# CTRL_Paws.net
KiCad netlist of a schematic drawn in EasyEDA Pro
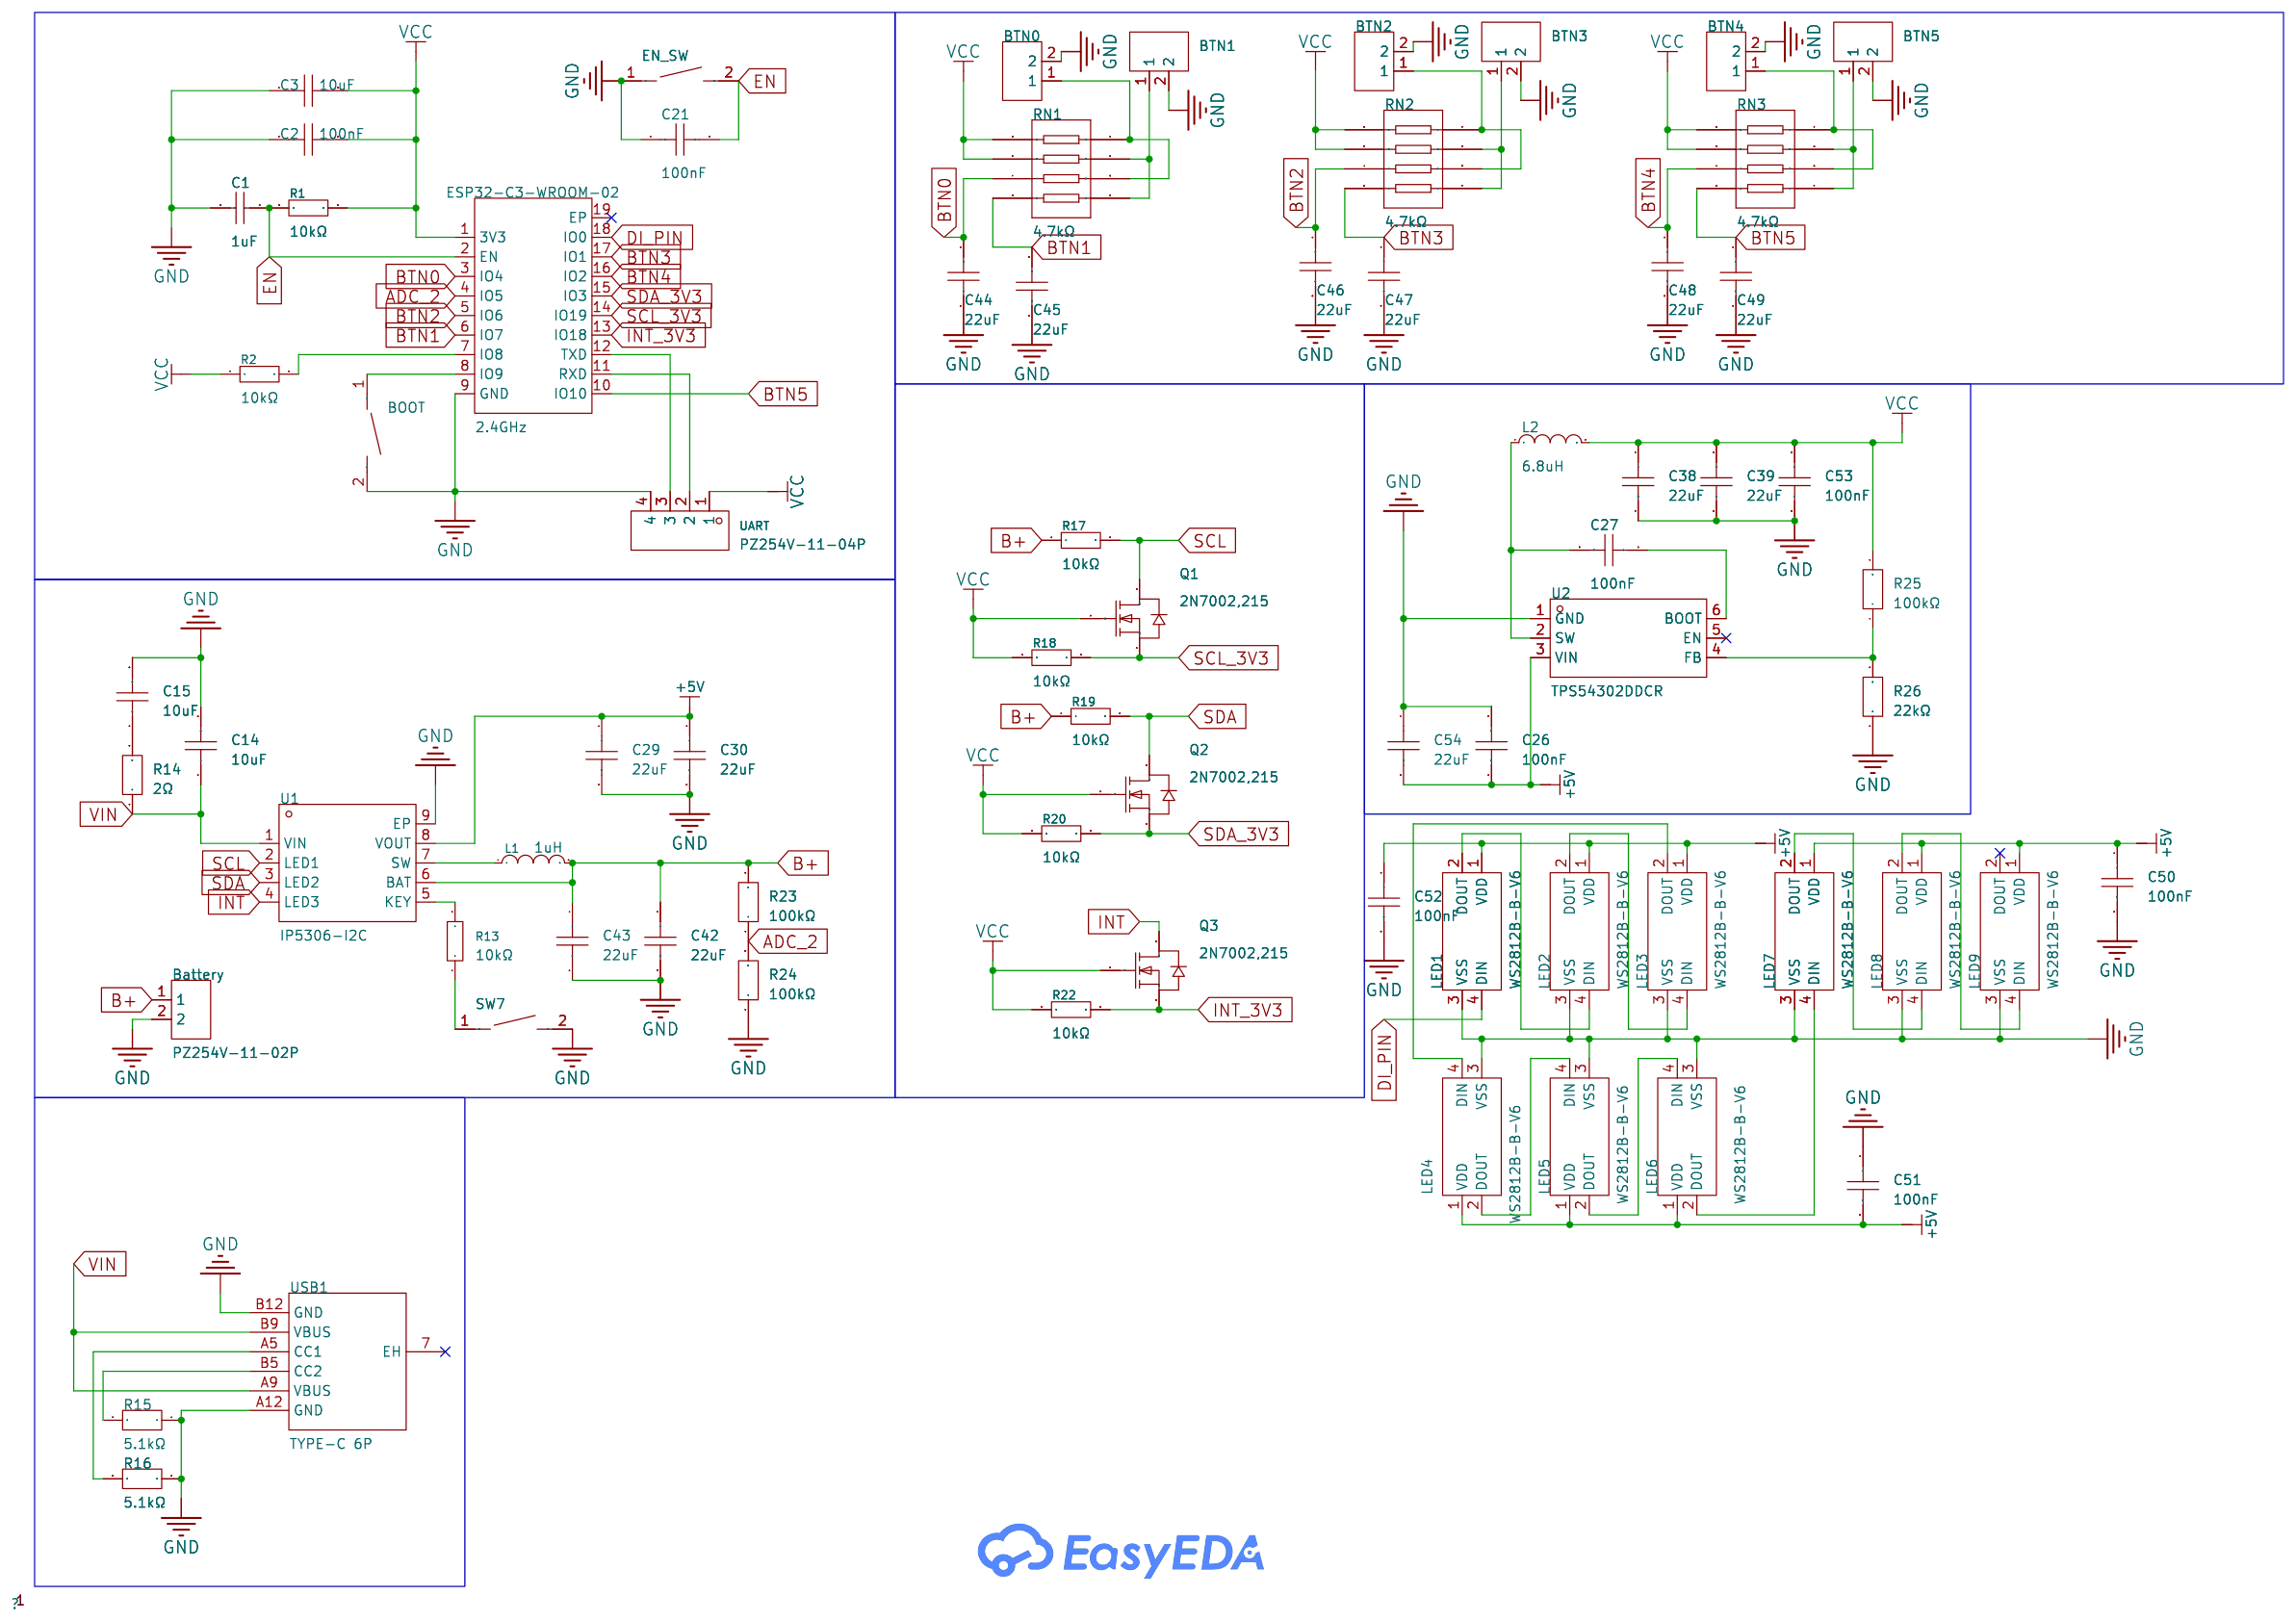
[diagram p0: schematic sheet]

(export (version "E")
  (design (tool "Eeschema 10.0.6"))
  (components
    (comp (ref "Battery")
      (value "PZ254V-11-02P")
      (footprint "easyedapro:HDR-TH_2P-P2.54-V-M")
      (fields (field (name "Manufacturer") "XFCN(兴飞)"))
      (libsource (lib "easyedapro") (part "PZ254V-11-02P"))
    )
    (comp (ref "BOOT")
      (value "TSA06154-050B832BA")
      (footprint "easyedapro:SW-TH_L6.1-W6.1-P5.00")
      (fields (field (name "Manufacturer") "Khon(康宏电子)"))
      (libsource (lib "easyedapro") (part "TSA06154-050B832BA"))
    )
    (comp (ref "BTN0")
      (value "PZ254V-11-02P")
      (footprint "easyedapro:HDR-TH_2P-P2.54-V-M")
      (fields (field (name "Manufacturer") "XFCN(兴飞)"))
      (libsource (lib "easyedapro") (part "PZ254V-11-02P"))
    )
    (comp (ref "BTN1")
      (value "PZ254V-11-02P")
      (footprint "easyedapro:HDR-TH_2P-P2.54-V-M")
      (fields (field (name "Manufacturer") "XFCN(兴飞)"))
      (libsource (lib "easyedapro") (part "PZ254V-11-02P"))
    )
    (comp (ref "BTN2")
      (value "PZ254V-11-02P")
      (footprint "easyedapro:HDR-TH_2P-P2.54-V-M")
      (fields (field (name "Manufacturer") "XFCN(兴飞)"))
      (libsource (lib "easyedapro") (part "PZ254V-11-02P"))
    )
    (comp (ref "BTN3")
      (value "PZ254V-11-02P")
      (footprint "easyedapro:HDR-TH_2P-P2.54-V-M")
      (fields (field (name "Manufacturer") "XFCN(兴飞)"))
      (libsource (lib "easyedapro") (part "PZ254V-11-02P"))
    )
    (comp (ref "BTN4")
      (value "PZ254V-11-02P")
      (footprint "easyedapro:HDR-TH_2P-P2.54-V-M")
      (fields (field (name "Manufacturer") "XFCN(兴飞)"))
      (libsource (lib "easyedapro") (part "PZ254V-11-02P"))
    )
    (comp (ref "BTN5")
      (value "PZ254V-11-02P")
      (footprint "easyedapro:HDR-TH_2P-P2.54-V-M")
      (fields (field (name "Manufacturer") "XFCN(兴飞)"))
      (libsource (lib "easyedapro") (part "PZ254V-11-02P"))
    )
    (comp (ref "C1")
      (value "1uF")
      (footprint "easyedapro:C0603")
      (description "Capacitance:1uF Tolerance:±10% Tolerance:±10% Voltage Rating:16V Temperature Coefficient:X7R")
      (fields
        (field (name "Manufacturer Part") "CL10B105KO8NNNC")
        (field (name "Manufacturer") "SAMSUNG(三星)")
      )
      (libsource (lib "easyedapro") (part "CL10B105KO8NNNC"))
    )
    (comp (ref "C2")
      (value "100nF")
      (footprint "easyedapro:C1206")
      (description "Capacitance:100nF Tolerance:±10% Tolerance:±10% Voltage Rating:16V Temperature Coefficient:X7R")
      (fields
        (field (name "Manufacturer Part") "CC1206KRX7R7BB104")
        (field (name "Manufacturer") "YAGEO(国巨)")
      )
      (libsource (lib "easyedapro") (part "CC1206KRX7R7BB104"))
    )
    (comp (ref "C3")
      (value "10uF")
      (footprint "easyedapro:C0603")
      (description "Capacitance:10uF Tolerance:±10% Tolerance:±10% Voltage Rating:16V Temperature Coefficient:X5R")
      (fields
        (field (name "Manufacturer Part") "CL10A106KO8NQNC")
        (field (name "Manufacturer") "SAMSUNG(三星)")
      )
      (libsource (lib "easyedapro") (part "CL10A106KO8NQNC"))
    )
    (comp (ref "C14")
      (value "10uF")
      (footprint "easyedapro:C0603")
      (description "Capacitance:10uF Tolerance:±10% Tolerance:±10% Voltage Rating:16V Temperature Coefficient:X5R")
      (fields
        (field (name "Manufacturer Part") "CL10A106KO8NQNC")
        (field (name "Manufacturer") "SAMSUNG(三星)")
      )
      (libsource (lib "easyedapro") (part "CL10A106KO8NQNC"))
    )
    (comp (ref "C15")
      (value "10uF")
      (footprint "easyedapro:C0603")
      (description "Capacitance:10uF Tolerance:±10% Tolerance:±10% Voltage Rating:16V Temperature Coefficient:X5R")
      (fields
        (field (name "Manufacturer Part") "CL10A106KO8NQNC")
        (field (name "Manufacturer") "SAMSUNG(三星)")
      )
      (libsource (lib "easyedapro") (part "CL10A106KO8NQNC"))
    )
    (comp (ref "C21")
      (value "100nF")
      (footprint "easyedapro:C1206")
      (description "Capacitance:100nF Tolerance:±10% Tolerance:±10% Voltage Rating:16V Temperature Coefficient:X7R")
      (fields
        (field (name "Manufacturer Part") "CC1206KRX7R7BB104")
        (field (name "Manufacturer") "YAGEO(国巨)")
      )
      (libsource (lib "easyedapro") (part "CC1206KRX7R7BB104"))
    )
    (comp (ref "C26")
      (value "100nF")
      (footprint "easyedapro:C1206")
      (description "Capacitance:100nF Tolerance:±10% Tolerance:±10% Voltage Rating:16V Temperature Coefficient:X7R")
      (fields
        (field (name "Manufacturer Part") "CC1206KRX7R7BB104")
        (field (name "Manufacturer") "YAGEO(国巨)")
      )
      (libsource (lib "easyedapro") (part "CC1206KRX7R7BB104"))
    )
    (comp (ref "C27")
      (value "100nF")
      (footprint "easyedapro:C1206")
      (description "Capacitance:100nF Tolerance:±10% Tolerance:±10% Voltage Rating:16V Temperature Coefficient:X7R")
      (fields
        (field (name "Manufacturer Part") "CC1206KRX7R7BB104")
        (field (name "Manufacturer") "YAGEO(国巨)")
      )
      (libsource (lib "easyedapro") (part "CC1206KRX7R7BB104"))
    )
    (comp (ref "C29")
      (value "22uF")
      (footprint "easyedapro:C0603")
      (description "Capacitance:22uF Tolerance:±20% Tolerance:±20% Voltage Rating:16V Temperature Coefficient:X5R")
      (fields
        (field (name "Manufacturer Part") "CL10A226MO7JZNC")
        (field (name "Manufacturer") "SAMSUNG(三星)")
      )
      (libsource (lib "easyedapro") (part "CL10A226MO7JZNC"))
    )
    (comp (ref "C30")
      (value "22uF")
      (footprint "easyedapro:C0603")
      (description "Capacitance:22uF Tolerance:±20% Tolerance:±20% Voltage Rating:16V Temperature Coefficient:X5R")
      (fields
        (field (name "Manufacturer Part") "CL10A226MO7JZNC")
        (field (name "Manufacturer") "SAMSUNG(三星)")
      )
      (libsource (lib "easyedapro") (part "CL10A226MO7JZNC"))
    )
    (comp (ref "C38")
      (value "22uF")
      (footprint "easyedapro:C0603")
      (description "Capacitance:22uF Tolerance:±20% Tolerance:±20% Voltage Rating:16V Temperature Coefficient:X5R")
      (fields
        (field (name "Manufacturer Part") "CL10A226MO7JZNC")
        (field (name "Manufacturer") "SAMSUNG(三星)")
      )
      (libsource (lib "easyedapro") (part "CL10A226MO7JZNC"))
    )
    (comp (ref "C39")
      (value "22uF")
      (footprint "easyedapro:C0603")
      (description "Capacitance:22uF Tolerance:±20% Tolerance:±20% Voltage Rating:16V Temperature Coefficient:X5R")
      (fields
        (field (name "Manufacturer Part") "CL10A226MO7JZNC")
        (field (name "Manufacturer") "SAMSUNG(三星)")
      )
      (libsource (lib "easyedapro") (part "CL10A226MO7JZNC"))
    )
    (comp (ref "C42")
      (value "22uF")
      (footprint "easyedapro:C0603")
      (description "Capacitance:22uF Tolerance:±20% Tolerance:±20% Voltage Rating:16V Temperature Coefficient:X5R")
      (fields
        (field (name "Manufacturer Part") "CL10A226MO7JZNC")
        (field (name "Manufacturer") "SAMSUNG(三星)")
      )
      (libsource (lib "easyedapro") (part "CL10A226MO7JZNC"))
    )
    (comp (ref "C43")
      (value "22uF")
      (footprint "easyedapro:C0603")
      (description "Capacitance:22uF Tolerance:±20% Tolerance:±20% Voltage Rating:16V Temperature Coefficient:X5R")
      (fields
        (field (name "Manufacturer Part") "CL10A226MO7JZNC")
        (field (name "Manufacturer") "SAMSUNG(三星)")
      )
      (libsource (lib "easyedapro") (part "CL10A226MO7JZNC"))
    )
    (comp (ref "C44")
      (value "22uF")
      (footprint "easyedapro:C0603")
      (description "Capacitance:22uF Tolerance:±20% Tolerance:±20% Voltage Rating:16V Temperature Coefficient:X5R")
      (fields
        (field (name "Manufacturer Part") "CL10A226MO7JZNC")
        (field (name "Manufacturer") "SAMSUNG(三星)")
      )
      (libsource (lib "easyedapro") (part "CL10A226MO7JZNC"))
    )
    (comp (ref "C45")
      (value "22uF")
      (footprint "easyedapro:C0603")
      (description "Capacitance:22uF Tolerance:±20% Tolerance:±20% Voltage Rating:16V Temperature Coefficient:X5R")
      (fields
        (field (name "Manufacturer Part") "CL10A226MO7JZNC")
        (field (name "Manufacturer") "SAMSUNG(三星)")
      )
      (libsource (lib "easyedapro") (part "CL10A226MO7JZNC"))
    )
    (comp (ref "C46")
      (value "22uF")
      (footprint "easyedapro:C0603")
      (description "Capacitance:22uF Tolerance:±20% Tolerance:±20% Voltage Rating:16V Temperature Coefficient:X5R")
      (fields
        (field (name "Manufacturer Part") "CL10A226MO7JZNC")
        (field (name "Manufacturer") "SAMSUNG(三星)")
      )
      (libsource (lib "easyedapro") (part "CL10A226MO7JZNC"))
    )
    (comp (ref "C47")
      (value "22uF")
      (footprint "easyedapro:C0603")
      (description "Capacitance:22uF Tolerance:±20% Tolerance:±20% Voltage Rating:16V Temperature Coefficient:X5R")
      (fields
        (field (name "Manufacturer Part") "CL10A226MO7JZNC")
        (field (name "Manufacturer") "SAMSUNG(三星)")
      )
      (libsource (lib "easyedapro") (part "CL10A226MO7JZNC"))
    )
    (comp (ref "C48")
      (value "22uF")
      (footprint "easyedapro:C0603")
      (description "Capacitance:22uF Tolerance:±20% Tolerance:±20% Voltage Rating:16V Temperature Coefficient:X5R")
      (fields
        (field (name "Manufacturer Part") "CL10A226MO7JZNC")
        (field (name "Manufacturer") "SAMSUNG(三星)")
      )
      (libsource (lib "easyedapro") (part "CL10A226MO7JZNC"))
    )
    (comp (ref "C49")
      (value "22uF")
      (footprint "easyedapro:C0603")
      (description "Capacitance:22uF Tolerance:±20% Tolerance:±20% Voltage Rating:16V Temperature Coefficient:X5R")
      (fields
        (field (name "Manufacturer Part") "CL10A226MO7JZNC")
        (field (name "Manufacturer") "SAMSUNG(三星)")
      )
      (libsource (lib "easyedapro") (part "CL10A226MO7JZNC"))
    )
    (comp (ref "C50")
      (value "100nF")
      (footprint "easyedapro:C1206")
      (description "Capacitance:100nF Tolerance:±10% Tolerance:±10% Voltage Rating:16V Temperature Coefficient:X7R")
      (fields
        (field (name "Manufacturer Part") "CC1206KRX7R7BB104")
        (field (name "Manufacturer") "YAGEO(国巨)")
      )
      (libsource (lib "easyedapro") (part "CC1206KRX7R7BB104"))
    )
    (comp (ref "C51")
      (value "100nF")
      (footprint "easyedapro:C1206")
      (description "Capacitance:100nF Tolerance:±10% Tolerance:±10% Voltage Rating:16V Temperature Coefficient:X7R")
      (fields
        (field (name "Manufacturer Part") "CC1206KRX7R7BB104")
        (field (name "Manufacturer") "YAGEO(国巨)")
      )
      (libsource (lib "easyedapro") (part "CC1206KRX7R7BB104"))
    )
    (comp (ref "C52")
      (value "100nF")
      (footprint "easyedapro:C1206")
      (description "Capacitance:100nF Tolerance:±10% Tolerance:±10% Voltage Rating:16V Temperature Coefficient:X7R")
      (fields
        (field (name "Manufacturer Part") "CC1206KRX7R7BB104")
        (field (name "Manufacturer") "YAGEO(国巨)")
      )
      (libsource (lib "easyedapro") (part "CC1206KRX7R7BB104"))
    )
    (comp (ref "C53")
      (value "100nF")
      (footprint "easyedapro:C1206")
      (description "Capacitance:100nF Tolerance:±10% Tolerance:±10% Voltage Rating:16V Temperature Coefficient:X7R")
      (fields
        (field (name "Manufacturer Part") "CC1206KRX7R7BB104")
        (field (name "Manufacturer") "YAGEO(国巨)")
      )
      (libsource (lib "easyedapro") (part "CC1206KRX7R7BB104"))
    )
    (comp (ref "C54")
      (value "22uF")
      (footprint "easyedapro:C0603")
      (description "Capacitance:22uF Tolerance:±20% Tolerance:±20% Voltage Rating:16V Temperature Coefficient:X5R")
      (fields
        (field (name "Manufacturer Part") "CL10A226MO7JZNC")
        (field (name "Manufacturer") "SAMSUNG(三星)")
      )
      (libsource (lib "easyedapro") (part "CL10A226MO7JZNC"))
    )
    (comp (ref "EN_SW")
      (value "TSA06154-050B832BA")
      (footprint "easyedapro:SW-TH_L6.1-W6.1-P5.00")
      (fields (field (name "Manufacturer") "Khon(康宏电子)"))
      (libsource (lib "easyedapro") (part "TSA06154-050B832BA"))
    )
    (comp (ref "ESP32-C3-WROOM-02")
      (value "2.4GHz")
      (footprint "easyedapro:BULETM-SMD_ESPRESSIF_ESP32-C3-WROOM-02-N4-4MB")
      (fields
        (field (name "Manufacturer Part") "ESP32-C3-WROOM-02-N4")
        (field (name "Manufacturer") "ESPRESSIF(乐鑫)")
      )
      (libsource (lib "easyedapro") (part "ESP32-C3-WROOM-02-N4(4MB)"))
    )
    (comp (ref "L1")
      (value "1uH")
      (footprint "easyedapro:IND-SMD_L7.2-W6.6_GPSR07X0")
      (fields (field (name "Manufacturer Part") "CYA0650-1.0UH") (field (name "Manufacturer") "SHOU HAN(首韩)"))
      (libsource (lib "easyedapro") (part "CYA0650-1.0UH"))
    )
    (comp (ref "L2")
      (value "6.8uH")
      (footprint "easyedapro:IND-SMD_L5.6-W5.2_DH0530H-100M")
      (fields (field (name "Manufacturer Part") "DH0530H-6R8M") (field (name "Manufacturer") "DH(德鸿感应)"))
      (libsource (lib "easyedapro") (part "DH0530H-6R8M"))
    )
    (comp (ref "LED1")
      (value "WS2812B-B-V6")
      (footprint "easyedapro:LED-SMD_4P-L5.0-W5.0-TL_WS2812B-B")
      (fields (field (name "Manufacturer") "worldsemi"))
      (libsource (lib "easyedapro") (part "WS2812B-B-V6"))
    )
    (comp (ref "LED2")
      (value "WS2812B-B-V6")
      (footprint "easyedapro:LED-SMD_4P-L5.0-W5.0-TL_WS2812B-B")
      (fields (field (name "Manufacturer") "worldsemi"))
      (libsource (lib "easyedapro") (part "WS2812B-B-V6"))
    )
    (comp (ref "LED3")
      (value "WS2812B-B-V6")
      (footprint "easyedapro:LED-SMD_4P-L5.0-W5.0-TL_WS2812B-B")
      (fields (field (name "Manufacturer") "worldsemi"))
      (libsource (lib "easyedapro") (part "WS2812B-B-V6"))
    )
    (comp (ref "LED4")
      (value "WS2812B-B-V6")
      (footprint "easyedapro:LED-SMD_4P-L5.0-W5.0-TL_WS2812B-B")
      (fields (field (name "Manufacturer") "worldsemi"))
      (libsource (lib "easyedapro") (part "WS2812B-B-V6"))
    )
    (comp (ref "LED5")
      (value "WS2812B-B-V6")
      (footprint "easyedapro:LED-SMD_4P-L5.0-W5.0-TL_WS2812B-B")
      (fields (field (name "Manufacturer") "worldsemi"))
      (libsource (lib "easyedapro") (part "WS2812B-B-V6"))
    )
    (comp (ref "LED6")
      (value "WS2812B-B-V6")
      (footprint "easyedapro:LED-SMD_4P-L5.0-W5.0-TL_WS2812B-B")
      (fields (field (name "Manufacturer") "worldsemi"))
      (libsource (lib "easyedapro") (part "WS2812B-B-V6"))
    )
    (comp (ref "LED7")
      (value "WS2812B-B-V6")
      (footprint "easyedapro:LED-SMD_4P-L5.0-W5.0-TL_WS2812B-B")
      (fields (field (name "Manufacturer") "worldsemi"))
      (libsource (lib "easyedapro") (part "WS2812B-B-V6"))
    )
    (comp (ref "LED8")
      (value "WS2812B-B-V6")
      (footprint "easyedapro:LED-SMD_4P-L5.0-W5.0-TL_WS2812B-B")
      (fields (field (name "Manufacturer") "worldsemi"))
      (libsource (lib "easyedapro") (part "WS2812B-B-V6"))
    )
    (comp (ref "LED9")
      (value "WS2812B-B-V6")
      (footprint "easyedapro:LED-SMD_4P-L5.0-W5.0-TL_WS2812B-B")
      (fields (field (name "Manufacturer") "worldsemi"))
      (libsource (lib "easyedapro") (part "WS2812B-B-V6"))
    )
    (comp (ref "Q1")
      (value "2N7002,215")
      (footprint "easyedapro:SOT-23_L2.9-W1.3-P1.90-LS2.4-BR")
      (fields (field (name "Manufacturer") "Nexperia(安世)"))
      (libsource (lib "easyedapro") (part "2N7002,215"))
    )
    (comp (ref "Q2")
      (value "2N7002,215")
      (footprint "easyedapro:SOT-23_L2.9-W1.3-P1.90-LS2.4-BR")
      (fields (field (name "Manufacturer") "Nexperia(安世)"))
      (libsource (lib "easyedapro") (part "2N7002,215"))
    )
    (comp (ref "Q3")
      (value "2N7002,215")
      (footprint "easyedapro:SOT-23_L2.9-W1.3-P1.90-LS2.4-BR")
      (fields (field (name "Manufacturer") "Nexperia(安世)"))
      (libsource (lib "easyedapro") (part "2N7002,215"))
    )
    (comp (ref "R1")
      (value "10kΩ")
      (footprint "easyedapro:R1206")
      (fields
        (field (name "Manufacturer Part") "1206W4F1002T5E")
        (field (name "Manufacturer") "UNI-ROYAL(厚声)")
      )
      (libsource (lib "easyedapro") (part "1206W4F1002T5E"))
    )
    (comp (ref "R2")
      (value "10kΩ")
      (footprint "easyedapro:R1206")
      (fields
        (field (name "Manufacturer Part") "1206W4F1002T5E")
        (field (name "Manufacturer") "UNI-ROYAL(厚声)")
      )
      (libsource (lib "easyedapro") (part "1206W4F1002T5E"))
    )
    (comp (ref "R13")
      (value "10kΩ")
      (footprint "easyedapro:R1206")
      (fields
        (field (name "Manufacturer Part") "1206W4F1002T5E")
        (field (name "Manufacturer") "UNI-ROYAL(厚声)")
      )
      (libsource (lib "easyedapro") (part "1206W4F1002T5E"))
    )
    (comp (ref "R14")
      (value "2Ω")
      (footprint "easyedapro:R1206")
      (fields (field (name "Manufacturer Part") "FRC1206F2R00TS") (field (name "Manufacturer") "FOJAN(富捷)"))
      (libsource (lib "easyedapro") (part "FRC1206F2R00TS"))
    )
    (comp (ref "R15")
      (value "5.1kΩ")
      (footprint "easyedapro:R1206")
      (fields (field (name "Manufacturer Part") "FRC1206J512 TS") (field (name "Manufacturer") "FOJAN(富捷)"))
      (libsource (lib "easyedapro") (part "FRC1206J512 TS"))
    )
    (comp (ref "R16")
      (value "5.1kΩ")
      (footprint "easyedapro:R1206")
      (fields (field (name "Manufacturer Part") "FRC1206J512 TS") (field (name "Manufacturer") "FOJAN(富捷)"))
      (libsource (lib "easyedapro") (part "FRC1206J512 TS"))
    )
    (comp (ref "R17")
      (value "10kΩ")
      (footprint "easyedapro:R1206")
      (fields
        (field (name "Manufacturer Part") "1206W4F1002T5E")
        (field (name "Manufacturer") "UNI-ROYAL(厚声)")
      )
      (libsource (lib "easyedapro") (part "1206W4F1002T5E"))
    )
    (comp (ref "R18")
      (value "10kΩ")
      (footprint "easyedapro:R1206")
      (fields
        (field (name "Manufacturer Part") "1206W4F1002T5E")
        (field (name "Manufacturer") "UNI-ROYAL(厚声)")
      )
      (libsource (lib "easyedapro") (part "1206W4F1002T5E"))
    )
    (comp (ref "R19")
      (value "10kΩ")
      (footprint "easyedapro:R1206")
      (fields
        (field (name "Manufacturer Part") "1206W4F1002T5E")
        (field (name "Manufacturer") "UNI-ROYAL(厚声)")
      )
      (libsource (lib "easyedapro") (part "1206W4F1002T5E"))
    )
    (comp (ref "R20")
      (value "10kΩ")
      (footprint "easyedapro:R1206")
      (fields
        (field (name "Manufacturer Part") "1206W4F1002T5E")
        (field (name "Manufacturer") "UNI-ROYAL(厚声)")
      )
      (libsource (lib "easyedapro") (part "1206W4F1002T5E"))
    )
    (comp (ref "R22")
      (value "10kΩ")
      (footprint "easyedapro:R1206")
      (fields
        (field (name "Manufacturer Part") "1206W4F1002T5E")
        (field (name "Manufacturer") "UNI-ROYAL(厚声)")
      )
      (libsource (lib "easyedapro") (part "1206W4F1002T5E"))
    )
    (comp (ref "R23")
      (value "100kΩ")
      (footprint "easyedapro:R0603")
      (fields (field (name "Manufacturer Part") "FRC0603J104 TS") (field (name "Manufacturer") "FOJAN(富捷)"))
      (libsource (lib "easyedapro") (part "FRC0603J104 TS"))
    )
    (comp (ref "R24")
      (value "100kΩ")
      (footprint "easyedapro:R0603")
      (fields (field (name "Manufacturer Part") "FRC0603J104 TS") (field (name "Manufacturer") "FOJAN(富捷)"))
      (libsource (lib "easyedapro") (part "FRC0603J104 TS"))
    )
    (comp (ref "R25")
      (value "100kΩ")
      (footprint "easyedapro:R0603")
      (fields (field (name "Manufacturer Part") "FRC0603J104 TS") (field (name "Manufacturer") "FOJAN(富捷)"))
      (libsource (lib "easyedapro") (part "FRC0603J104 TS"))
    )
    (comp (ref "R26")
      (value "22kΩ")
      (footprint "easyedapro:R0603")
      (fields (field (name "Manufacturer Part") "FRC0603F2202TS") (field (name "Manufacturer") "FOJAN(富捷)"))
      (libsource (lib "easyedapro") (part "FRC0603F2202TS"))
    )
    (comp (ref "RN1")
      (value "4.7kΩ")
      (footprint "easyedapro:RES-ARRAY-SMD_0603-8P-L3.2-W1.6-BL")
      (fields (field (name "Manufacturer Part") "YC164-JR-074K7L") (field (name "Manufacturer") "YAGEO(国巨)"))
      (libsource (lib "easyedapro") (part "YC164-JR-074K7L"))
    )
    (comp (ref "RN2")
      (value "4.7kΩ")
      (footprint "easyedapro:RES-ARRAY-SMD_0603-8P-L3.2-W1.6-BL")
      (fields (field (name "Manufacturer Part") "YC164-JR-074K7L") (field (name "Manufacturer") "YAGEO(国巨)"))
      (libsource (lib "easyedapro") (part "YC164-JR-074K7L"))
    )
    (comp (ref "RN3")
      (value "4.7kΩ")
      (footprint "easyedapro:RES-ARRAY-SMD_0603-8P-L3.2-W1.6-BL")
      (fields (field (name "Manufacturer Part") "YC164-JR-074K7L") (field (name "Manufacturer") "YAGEO(国巨)"))
      (libsource (lib "easyedapro") (part "YC164-JR-074K7L"))
    )
    (comp (ref "SW7")
      (value "TSA06154-050B832BA")
      (footprint "easyedapro:SW-TH_L6.1-W6.1-P5.00")
      (fields (field (name "Manufacturer") "Khon(康宏电子)"))
      (libsource (lib "easyedapro") (part "TSA06154-050B832BA"))
    )
    (comp (ref "U1")
      (value "IP5306-I2C")
      (footprint "easyedapro:ESOP-8_L4.9-W3.9-P1.27-LS6.0-BL-EP2.0")
      (fields (field (name "Manufacturer") "INJOINIC(英集芯)"))
      (libsource (lib "easyedapro") (part "IP5306-I2C"))
    )
    (comp (ref "U2")
      (value "TPS54302DDCR")
      (footprint "easyedapro:SOT-23-6_L2.9-W1.6-P0.95-LS2.8-BL")
      (fields (field (name "Manufacturer") "TI(德州仪器)"))
      (libsource (lib "easyedapro") (part "TPS54302DDCR_C311983"))
    )
    (comp (ref "UART")
      (value "PZ254V-11-04P")
      (footprint "easyedapro:HDR-TH_4P-P2.54-V-M")
      (fields (field (name "Manufacturer") "XFCN(兴飞)"))
      (libsource (lib "easyedapro") (part "PZ254V-11-04P_C2691448"))
    )
    (comp (ref "USB1")
      (value "TYPE-C 6P")
      (footprint "easyedapro:TYPE-C-SMD_TYPE-C-6P_1")
      (fields (field (name "Manufacturer") "SHOU HAN(首韩)"))
      (libsource (lib "easyedapro") (part "TYPE-C 6P"))
    )
  )
  (nets
    (net (code "1") (name "+5V") (class "Default")
      (node (ref "C26") (pin "1") (pinfunction "1_1") (pintype "unspecified"))
      (node (ref "C29") (pin "1") (pinfunction "1_1") (pintype "unspecified"))
      (node (ref "C30") (pin "1") (pinfunction "1_1") (pintype "unspecified"))
      (node (ref "C50") (pin "1") (pinfunction "1_1") (pintype "unspecified"))
      (node (ref "C51") (pin "2") (pinfunction "2_2") (pintype "unspecified"))
      (node (ref "C52") (pin "1") (pinfunction "1_1") (pintype "unspecified"))
      (node (ref "C54") (pin "2") (pinfunction "2_2") (pintype "unspecified"))
      (node (ref "LED1") (pin "1") (pinfunction "VDD_1") (pintype "unspecified"))
      (node (ref "LED2") (pin "1") (pinfunction "VDD_1") (pintype "unspecified"))
      (node (ref "LED3") (pin "1") (pinfunction "VDD_1") (pintype "unspecified"))
      (node (ref "LED4") (pin "1") (pinfunction "VDD_1") (pintype "unspecified"))
      (node (ref "LED5") (pin "1") (pinfunction "VDD_1") (pintype "unspecified"))
      (node (ref "LED6") (pin "1") (pinfunction "VDD_1") (pintype "unspecified"))
      (node (ref "LED7") (pin "1") (pinfunction "VDD_1") (pintype "unspecified"))
      (node (ref "LED8") (pin "1") (pinfunction "VDD_1") (pintype "unspecified"))
      (node (ref "LED9") (pin "1") (pinfunction "VDD_1") (pintype "unspecified"))
      (node (ref "U1") (pin "8") (pinfunction "VOUT_8") (pintype "unspecified"))
      (node (ref "U2") (pin "3") (pinfunction "VIN_3") (pintype "unspecified"))
    )
    (net (code "2") (name "ADC_2") (class "Default")
      (node (ref "ESP32-C3-WROOM-02") (pin "4") (pinfunction "IO5_4") (pintype "unspecified"))
      (node (ref "R23") (pin "1") (pinfunction "1_1") (pintype "unspecified"))
      (node (ref "R24") (pin "2") (pinfunction "2_2") (pintype "unspecified"))
    )
    (net (code "3") (name "B+") (class "Default")
      (node (ref "Battery") (pin "1") (pinfunction "1_1") (pintype "unspecified"))
      (node (ref "C42") (pin "1") (pinfunction "1_1") (pintype "unspecified"))
      (node (ref "C43") (pin "1") (pinfunction "1_1") (pintype "unspecified"))
      (node (ref "L1") (pin "2") (pinfunction "2_2") (pintype "input"))
      (node (ref "R17") (pin "1") (pinfunction "1_1") (pintype "input"))
      (node (ref "R19") (pin "1") (pinfunction "1_1") (pintype "input"))
      (node (ref "R23") (pin "2") (pinfunction "2_2") (pintype "unspecified"))
      (node (ref "U1") (pin "6") (pinfunction "BAT_6") (pintype "unspecified"))
    )
    (net (code "4") (name "BTN0") (class "Default")
      (node (ref "C44") (pin "1") (pinfunction "1_1") (pintype "unspecified"))
      (node (ref "ESP32-C3-WROOM-02") (pin "3") (pinfunction "IO4_3") (pintype "unspecified"))
      (node (ref "RN1") (pin "7") (pinfunction "7_7") (pintype "input"))
    )
    (net (code "5") (name "BTN1") (class "Default")
      (node (ref "C45") (pin "1") (pinfunction "1_1") (pintype "unspecified"))
      (node (ref "ESP32-C3-WROOM-02") (pin "6") (pinfunction "IO7_6") (pintype "unspecified"))
      (node (ref "RN1") (pin "8") (pinfunction "8_8") (pintype "input"))
    )
    (net (code "6") (name "BTN2") (class "Default")
      (node (ref "C46") (pin "1") (pinfunction "1_1") (pintype "unspecified"))
      (node (ref "ESP32-C3-WROOM-02") (pin "5") (pinfunction "IO6_5") (pintype "unspecified"))
      (node (ref "RN2") (pin "7") (pinfunction "7_7") (pintype "input"))
    )
    (net (code "7") (name "BTN3") (class "Default")
      (node (ref "C47") (pin "1") (pinfunction "1_1") (pintype "unspecified"))
      (node (ref "ESP32-C3-WROOM-02") (pin "17") (pinfunction "IO1_17") (pintype "unspecified"))
      (node (ref "RN2") (pin "8") (pinfunction "8_8") (pintype "input"))
    )
    (net (code "8") (name "BTN4") (class "Default")
      (node (ref "C48") (pin "1") (pinfunction "1_1") (pintype "unspecified"))
      (node (ref "ESP32-C3-WROOM-02") (pin "16") (pinfunction "IO2_16") (pintype "unspecified"))
      (node (ref "RN3") (pin "7") (pinfunction "7_7") (pintype "input"))
    )
    (net (code "9") (name "BTN5") (class "Default")
      (node (ref "C49") (pin "1") (pinfunction "1_1") (pintype "unspecified"))
      (node (ref "ESP32-C3-WROOM-02") (pin "10") (pinfunction "IO10_10") (pintype "unspecified"))
      (node (ref "RN3") (pin "8") (pinfunction "8_8") (pintype "input"))
    )
    (net (code "10") (name "DI_PIN") (class "Default")
      (node (ref "ESP32-C3-WROOM-02") (pin "18") (pinfunction "IO0_18") (pintype "unspecified"))
      (node (ref "LED1") (pin "4") (pinfunction "DIN_4") (pintype "unspecified"))
    )
    (net (code "11") (name "EN") (class "Default")
      (node (ref "C1") (pin "2") (pinfunction "2_2") (pintype "input"))
      (node (ref "C21") (pin "2") (pinfunction "2_2") (pintype "unspecified"))
      (node (ref "EN_SW") (pin "2") (pinfunction "2_2") (pintype "unspecified"))
      (node (ref "ESP32-C3-WROOM-02") (pin "2") (pinfunction "EN_2") (pintype "unspecified"))
      (node (ref "R1") (pin "1") (pinfunction "1_1") (pintype "input"))
    )
    (net (code "12") (name "GND") (class "Default")
      (node (ref "BOOT") (pin "2") (pinfunction "2_2") (pintype "unspecified"))
      (node (ref "BTN0") (pin "2") (pinfunction "2_2") (pintype "unspecified"))
      (node (ref "BTN1") (pin "2") (pinfunction "2_2") (pintype "unspecified"))
      (node (ref "BTN2") (pin "2") (pinfunction "2_2") (pintype "unspecified"))
      (node (ref "BTN3") (pin "2") (pinfunction "2_2") (pintype "unspecified"))
      (node (ref "BTN4") (pin "2") (pinfunction "2_2") (pintype "unspecified"))
      (node (ref "BTN5") (pin "2") (pinfunction "2_2") (pintype "unspecified"))
      (node (ref "Battery") (pin "2") (pinfunction "2_2") (pintype "unspecified"))
      (node (ref "C1") (pin "1") (pinfunction "1_1") (pintype "input"))
      (node (ref "C14") (pin "2") (pinfunction "2_2") (pintype "unspecified"))
      (node (ref "C15") (pin "2") (pinfunction "2_2") (pintype "unspecified"))
      (node (ref "C2") (pin "1") (pinfunction "1_1") (pintype "unspecified"))
      (node (ref "C21") (pin "1") (pinfunction "1_1") (pintype "unspecified"))
      (node (ref "C26") (pin "2") (pinfunction "2_2") (pintype "unspecified"))
      (node (ref "C29") (pin "2") (pinfunction "2_2") (pintype "unspecified"))
      (node (ref "C3") (pin "1") (pinfunction "1_1") (pintype "unspecified"))
      (node (ref "C30") (pin "2") (pinfunction "2_2") (pintype "unspecified"))
      (node (ref "C38") (pin "2") (pinfunction "2_2") (pintype "unspecified"))
      (node (ref "C39") (pin "2") (pinfunction "2_2") (pintype "unspecified"))
      (node (ref "C42") (pin "2") (pinfunction "2_2") (pintype "unspecified"))
      (node (ref "C43") (pin "2") (pinfunction "2_2") (pintype "unspecified"))
      (node (ref "C44") (pin "2") (pinfunction "2_2") (pintype "unspecified"))
      (node (ref "C45") (pin "2") (pinfunction "2_2") (pintype "unspecified"))
      (node (ref "C46") (pin "2") (pinfunction "2_2") (pintype "unspecified"))
      (node (ref "C47") (pin "2") (pinfunction "2_2") (pintype "unspecified"))
      (node (ref "C48") (pin "2") (pinfunction "2_2") (pintype "unspecified"))
      (node (ref "C49") (pin "2") (pinfunction "2_2") (pintype "unspecified"))
      (node (ref "C50") (pin "2") (pinfunction "2_2") (pintype "unspecified"))
      (node (ref "C51") (pin "1") (pinfunction "1_1") (pintype "unspecified"))
      (node (ref "C52") (pin "2") (pinfunction "2_2") (pintype "unspecified"))
      (node (ref "C53") (pin "1") (pinfunction "1_1") (pintype "unspecified"))
      (node (ref "C54") (pin "1") (pinfunction "1_1") (pintype "unspecified"))
      (node (ref "EN_SW") (pin "1") (pinfunction "1_1") (pintype "unspecified"))
      (node (ref "ESP32-C3-WROOM-02") (pin "9") (pinfunction "GND_9") (pintype "unspecified"))
      (node (ref "LED1") (pin "3") (pinfunction "VSS_3") (pintype "unspecified"))
      (node (ref "LED2") (pin "3") (pinfunction "VSS_3") (pintype "unspecified"))
      (node (ref "LED3") (pin "3") (pinfunction "VSS_3") (pintype "unspecified"))
      (node (ref "LED4") (pin "3") (pinfunction "VSS_3") (pintype "unspecified"))
      (node (ref "LED5") (pin "3") (pinfunction "VSS_3") (pintype "unspecified"))
      (node (ref "LED6") (pin "3") (pinfunction "VSS_3") (pintype "unspecified"))
      (node (ref "LED7") (pin "3") (pinfunction "VSS_3") (pintype "unspecified"))
      (node (ref "LED8") (pin "3") (pinfunction "VSS_3") (pintype "unspecified"))
      (node (ref "LED9") (pin "3") (pinfunction "VSS_3") (pintype "unspecified"))
      (node (ref "R15") (pin "1") (pinfunction "1_1") (pintype "unspecified"))
      (node (ref "R16") (pin "1") (pinfunction "1_1") (pintype "unspecified"))
      (node (ref "R24") (pin "1") (pinfunction "1_1") (pintype "unspecified"))
      (node (ref "R26") (pin "1") (pinfunction "1_1") (pintype "unspecified"))
      (node (ref "SW7") (pin "2") (pinfunction "2_2") (pintype "unspecified"))
      (node (ref "U1") (pin "9") (pinfunction "EP_9") (pintype "unspecified"))
      (node (ref "U2") (pin "1") (pinfunction "GND_1") (pintype "unspecified"))
      (node (ref "UART") (pin "4") (pinfunction "4_4") (pintype "input"))
      (node (ref "USB1") (pin "A12") (pinfunction "GND_A12") (pintype "unspecified"))
      (node (ref "USB1") (pin "B12") (pinfunction "GND_B12") (pintype "unspecified"))
    )
    (net (code "13") (name "INT") (class "Default")
      (node (ref "Q3") (pin "3") (pinfunction "D_3") (pintype "unspecified"))
      (node (ref "U1") (pin "4") (pinfunction "LED3_4") (pintype "unspecified"))
    )
    (net (code "14") (name "INT_3V3") (class "Default")
      (node (ref "ESP32-C3-WROOM-02") (pin "13") (pinfunction "IO18_13") (pintype "unspecified"))
      (node (ref "Q3") (pin "2") (pinfunction "S_2") (pintype "unspecified"))
      (node (ref "R22") (pin "2") (pinfunction "2_2") (pintype "input"))
    )
    (net (code "15") (name "Net-(BTN0-Pad1)") (class "Default")
      (node (ref "BTN0") (pin "1") (pinfunction "1_1") (pintype "unspecified"))
      (node (ref "RN1") (pin "2") (pinfunction "2_2") (pintype "input"))
      (node (ref "RN1") (pin "4") (pinfunction "4_4") (pintype "input"))
    )
    (net (code "16") (name "Net-(BTN1-Pad1)") (class "Default")
      (node (ref "BTN1") (pin "1") (pinfunction "1_1") (pintype "unspecified"))
      (node (ref "RN1") (pin "1") (pinfunction "1_1") (pintype "input"))
      (node (ref "RN1") (pin "3") (pinfunction "3_3") (pintype "input"))
    )
    (net (code "17") (name "Net-(BTN2-Pad1)") (class "Default")
      (node (ref "BTN2") (pin "1") (pinfunction "1_1") (pintype "unspecified"))
      (node (ref "RN2") (pin "2") (pinfunction "2_2") (pintype "input"))
      (node (ref "RN2") (pin "4") (pinfunction "4_4") (pintype "input"))
    )
    (net (code "18") (name "Net-(BTN3-Pad1)") (class "Default")
      (node (ref "BTN3") (pin "1") (pinfunction "1_1") (pintype "unspecified"))
      (node (ref "RN2") (pin "1") (pinfunction "1_1") (pintype "input"))
      (node (ref "RN2") (pin "3") (pinfunction "3_3") (pintype "input"))
    )
    (net (code "19") (name "Net-(BTN4-Pad1)") (class "Default")
      (node (ref "BTN4") (pin "1") (pinfunction "1_1") (pintype "unspecified"))
      (node (ref "RN3") (pin "2") (pinfunction "2_2") (pintype "input"))
      (node (ref "RN3") (pin "4") (pinfunction "4_4") (pintype "input"))
    )
    (net (code "20") (name "Net-(BTN5-Pad1)") (class "Default")
      (node (ref "BTN5") (pin "1") (pinfunction "1_1") (pintype "unspecified"))
      (node (ref "RN3") (pin "1") (pinfunction "1_1") (pintype "input"))
      (node (ref "RN3") (pin "3") (pinfunction "3_3") (pintype "input"))
    )
    (net (code "21") (name "Net-(C15-Pad1)") (class "Default")
      (node (ref "C15") (pin "1") (pinfunction "1_1") (pintype "unspecified"))
      (node (ref "R14") (pin "2") (pinfunction "2_2") (pintype "unspecified"))
    )
    (net (code "22") (name "Net-(ESP32-C3-WROOM-02-IO8)") (class "Default")
      (node (ref "ESP32-C3-WROOM-02") (pin "7") (pinfunction "IO8_7") (pintype "unspecified"))
      (node (ref "R2") (pin "2") (pinfunction "2_2") (pintype "input"))
    )
    (net (code "23") (name "Net-(ESP32-C3-WROOM-02-IO9)") (class "Default")
      (node (ref "BOOT") (pin "1") (pinfunction "1_1") (pintype "unspecified"))
      (node (ref "ESP32-C3-WROOM-02") (pin "8") (pinfunction "IO9_8") (pintype "unspecified"))
    )
    (net (code "24") (name "Net-(ESP32-C3-WROOM-02-RXD)") (class "Default")
      (node (ref "ESP32-C3-WROOM-02") (pin "11") (pinfunction "RXD_11") (pintype "unspecified"))
      (node (ref "UART") (pin "2") (pinfunction "2_2") (pintype "input"))
    )
    (net (code "25") (name "Net-(ESP32-C3-WROOM-02-TXD)") (class "Default")
      (node (ref "ESP32-C3-WROOM-02") (pin "12") (pinfunction "TXD_12") (pintype "unspecified"))
      (node (ref "UART") (pin "3") (pinfunction "3_3") (pintype "input"))
    )
    (net (code "26") (name "Net-(LED1-DOUT)") (class "Default")
      (node (ref "LED1") (pin "2") (pinfunction "DOUT_2") (pintype "unspecified"))
      (node (ref "LED2") (pin "4") (pinfunction "DIN_4") (pintype "unspecified"))
    )
    (net (code "27") (name "Net-(LED2-DOUT)") (class "Default")
      (node (ref "LED2") (pin "2") (pinfunction "DOUT_2") (pintype "unspecified"))
      (node (ref "LED3") (pin "4") (pinfunction "DIN_4") (pintype "unspecified"))
    )
    (net (code "28") (name "Net-(LED3-DOUT)") (class "Default")
      (node (ref "LED3") (pin "2") (pinfunction "DOUT_2") (pintype "unspecified"))
      (node (ref "LED4") (pin "4") (pinfunction "DIN_4") (pintype "unspecified"))
    )
    (net (code "29") (name "Net-(LED4-DOUT)") (class "Default")
      (node (ref "LED4") (pin "2") (pinfunction "DOUT_2") (pintype "unspecified"))
      (node (ref "LED5") (pin "4") (pinfunction "DIN_4") (pintype "unspecified"))
    )
    (net (code "30") (name "Net-(LED5-DOUT)") (class "Default")
      (node (ref "LED5") (pin "2") (pinfunction "DOUT_2") (pintype "unspecified"))
      (node (ref "LED6") (pin "4") (pinfunction "DIN_4") (pintype "unspecified"))
    )
    (net (code "31") (name "Net-(LED6-DOUT)") (class "Default")
      (node (ref "LED6") (pin "2") (pinfunction "DOUT_2") (pintype "unspecified"))
      (node (ref "LED7") (pin "4") (pinfunction "DIN_4") (pintype "unspecified"))
    )
    (net (code "32") (name "Net-(LED7-DOUT)") (class "Default")
      (node (ref "LED7") (pin "2") (pinfunction "DOUT_2") (pintype "unspecified"))
      (node (ref "LED8") (pin "4") (pinfunction "DIN_4") (pintype "unspecified"))
    )
    (net (code "33") (name "Net-(LED8-DOUT)") (class "Default")
      (node (ref "LED8") (pin "2") (pinfunction "DOUT_2") (pintype "unspecified"))
      (node (ref "LED9") (pin "4") (pinfunction "DIN_4") (pintype "unspecified"))
    )
    (net (code "34") (name "Net-(R13-Pad1)") (class "Default")
      (node (ref "R13") (pin "1") (pinfunction "1_1") (pintype "input"))
      (node (ref "SW7") (pin "1") (pinfunction "1_1") (pintype "unspecified"))
    )
    (net (code "35") (name "Net-(U1-KEY)") (class "Default")
      (node (ref "R13") (pin "2") (pinfunction "2_2") (pintype "input"))
      (node (ref "U1") (pin "5") (pinfunction "KEY_5") (pintype "unspecified"))
    )
    (net (code "36") (name "Net-(U1-SW)") (class "Default")
      (node (ref "L1") (pin "1") (pinfunction "1_1") (pintype "input"))
      (node (ref "U1") (pin "7") (pinfunction "SW_7") (pintype "unspecified"))
    )
    (net (code "37") (name "Net-(U2-BOOT)") (class "Default")
      (node (ref "C27") (pin "1") (pinfunction "1_1") (pintype "unspecified"))
      (node (ref "U2") (pin "6") (pinfunction "BOOT_6") (pintype "unspecified"))
    )
    (net (code "38") (name "Net-(U2-FB)") (class "Default")
      (node (ref "R25") (pin "1") (pinfunction "1_1") (pintype "unspecified"))
      (node (ref "R26") (pin "2") (pinfunction "2_2") (pintype "unspecified"))
      (node (ref "U2") (pin "4") (pinfunction "FB_4") (pintype "unspecified"))
    )
    (net (code "39") (name "Net-(U2-SW)") (class "Default")
      (node (ref "C27") (pin "2") (pinfunction "2_2") (pintype "unspecified"))
      (node (ref "L2") (pin "1") (pinfunction "1_1") (pintype "unspecified"))
      (node (ref "U2") (pin "2") (pinfunction "SW_2") (pintype "unspecified"))
    )
    (net (code "40") (name "Net-(USB1-CC1)") (class "Default")
      (node (ref "R16") (pin "2") (pinfunction "2_2") (pintype "unspecified"))
      (node (ref "USB1") (pin "A5") (pinfunction "CC1_A5") (pintype "unspecified"))
    )
    (net (code "41") (name "Net-(USB1-CC2)") (class "Default")
      (node (ref "R15") (pin "2") (pinfunction "2_2") (pintype "unspecified"))
      (node (ref "USB1") (pin "B5") (pinfunction "CC2_B5") (pintype "unspecified"))
    )
    (net (code "42") (name "SCL") (class "Default")
      (node (ref "Q1") (pin "3") (pinfunction "D_3") (pintype "unspecified"))
      (node (ref "R17") (pin "2") (pinfunction "2_2") (pintype "input"))
      (node (ref "U1") (pin "2") (pinfunction "LED1_2") (pintype "unspecified"))
    )
    (net (code "43") (name "SCL_3V3") (class "Default")
      (node (ref "ESP32-C3-WROOM-02") (pin "14") (pinfunction "IO19_14") (pintype "unspecified"))
      (node (ref "Q1") (pin "2") (pinfunction "S_2") (pintype "unspecified"))
      (node (ref "R18") (pin "2") (pinfunction "2_2") (pintype "input"))
    )
    (net (code "44") (name "SDA") (class "Default")
      (node (ref "Q2") (pin "3") (pinfunction "D_3") (pintype "unspecified"))
      (node (ref "R19") (pin "2") (pinfunction "2_2") (pintype "input"))
      (node (ref "U1") (pin "3") (pinfunction "LED2_3") (pintype "unspecified"))
    )
    (net (code "45") (name "SDA_3V3") (class "Default")
      (node (ref "ESP32-C3-WROOM-02") (pin "15") (pinfunction "IO3_15") (pintype "unspecified"))
      (node (ref "Q2") (pin "2") (pinfunction "S_2") (pintype "unspecified"))
      (node (ref "R20") (pin "2") (pinfunction "2_2") (pintype "input"))
    )
    (net (code "46") (name "VCC") (class "Default")
      (node (ref "C2") (pin "2") (pinfunction "2_2") (pintype "unspecified"))
      (node (ref "C3") (pin "2") (pinfunction "2_2") (pintype "unspecified"))
      (node (ref "C38") (pin "1") (pinfunction "1_1") (pintype "unspecified"))
      (node (ref "C39") (pin "1") (pinfunction "1_1") (pintype "unspecified"))
      (node (ref "C53") (pin "2") (pinfunction "2_2") (pintype "unspecified"))
      (node (ref "ESP32-C3-WROOM-02") (pin "1") (pinfunction "3V3_1") (pintype "unspecified"))
      (node (ref "L2") (pin "2") (pinfunction "2_2") (pintype "unspecified"))
      (node (ref "Q1") (pin "1") (pinfunction "G_1") (pintype "unspecified"))
      (node (ref "Q2") (pin "1") (pinfunction "G_1") (pintype "unspecified"))
      (node (ref "Q3") (pin "1") (pinfunction "G_1") (pintype "unspecified"))
      (node (ref "R1") (pin "2") (pinfunction "2_2") (pintype "input"))
      (node (ref "R18") (pin "1") (pinfunction "1_1") (pintype "input"))
      (node (ref "R2") (pin "1") (pinfunction "1_1") (pintype "input"))
      (node (ref "R20") (pin "1") (pinfunction "1_1") (pintype "input"))
      (node (ref "R22") (pin "1") (pinfunction "1_1") (pintype "input"))
      (node (ref "R25") (pin "2") (pinfunction "2_2") (pintype "unspecified"))
      (node (ref "RN1") (pin "5") (pinfunction "5_5") (pintype "input"))
      (node (ref "RN1") (pin "6") (pinfunction "6_6") (pintype "input"))
      (node (ref "RN2") (pin "5") (pinfunction "5_5") (pintype "input"))
      (node (ref "RN2") (pin "6") (pinfunction "6_6") (pintype "input"))
      (node (ref "RN3") (pin "5") (pinfunction "5_5") (pintype "input"))
      (node (ref "RN3") (pin "6") (pinfunction "6_6") (pintype "input"))
      (node (ref "UART") (pin "1") (pinfunction "1_1") (pintype "input"))
    )
    (net (code "47") (name "VIN") (class "Default")
      (node (ref "C14") (pin "1") (pinfunction "1_1") (pintype "unspecified"))
      (node (ref "R14") (pin "1") (pinfunction "1_1") (pintype "unspecified"))
      (node (ref "U1") (pin "1") (pinfunction "VIN_1") (pintype "unspecified"))
      (node (ref "USB1") (pin "A9") (pinfunction "VBUS_A9") (pintype "unspecified"))
      (node (ref "USB1") (pin "B9") (pinfunction "VBUS_B9") (pintype "unspecified"))
    )
    (net (code "48") (name "unconnected-(ESP32-C3-WROOM-02-EP-Pad19)") (class "Default")
      (node (ref "ESP32-C3-WROOM-02") (pin "19") (pinfunction "EP_19") (pintype "unspecified+no_connect"))
    )
    (net (code "49") (name "unconnected-(LED9-DOUT-Pad2)") (class "Default")
      (node (ref "LED9") (pin "2") (pinfunction "DOUT_2") (pintype "unspecified+no_connect"))
    )
    (net (code "50") (name "unconnected-(U2-EN-Pad5)") (class "Default")
      (node (ref "U2") (pin "5") (pinfunction "EN_5") (pintype "unspecified+no_connect"))
    )
    (net (code "51") (name "unconnected-(USB1-EH-Pad7)") (class "Default")
      (node (ref "USB1") (pin "7") (pinfunction "EH_7") (pintype "unspecified+no_connect"))
    )
  )
)
